# SCH_MyBusinessCard_2024-10-20.net
KiCad netlist of a schematic drawn in EasyEDA
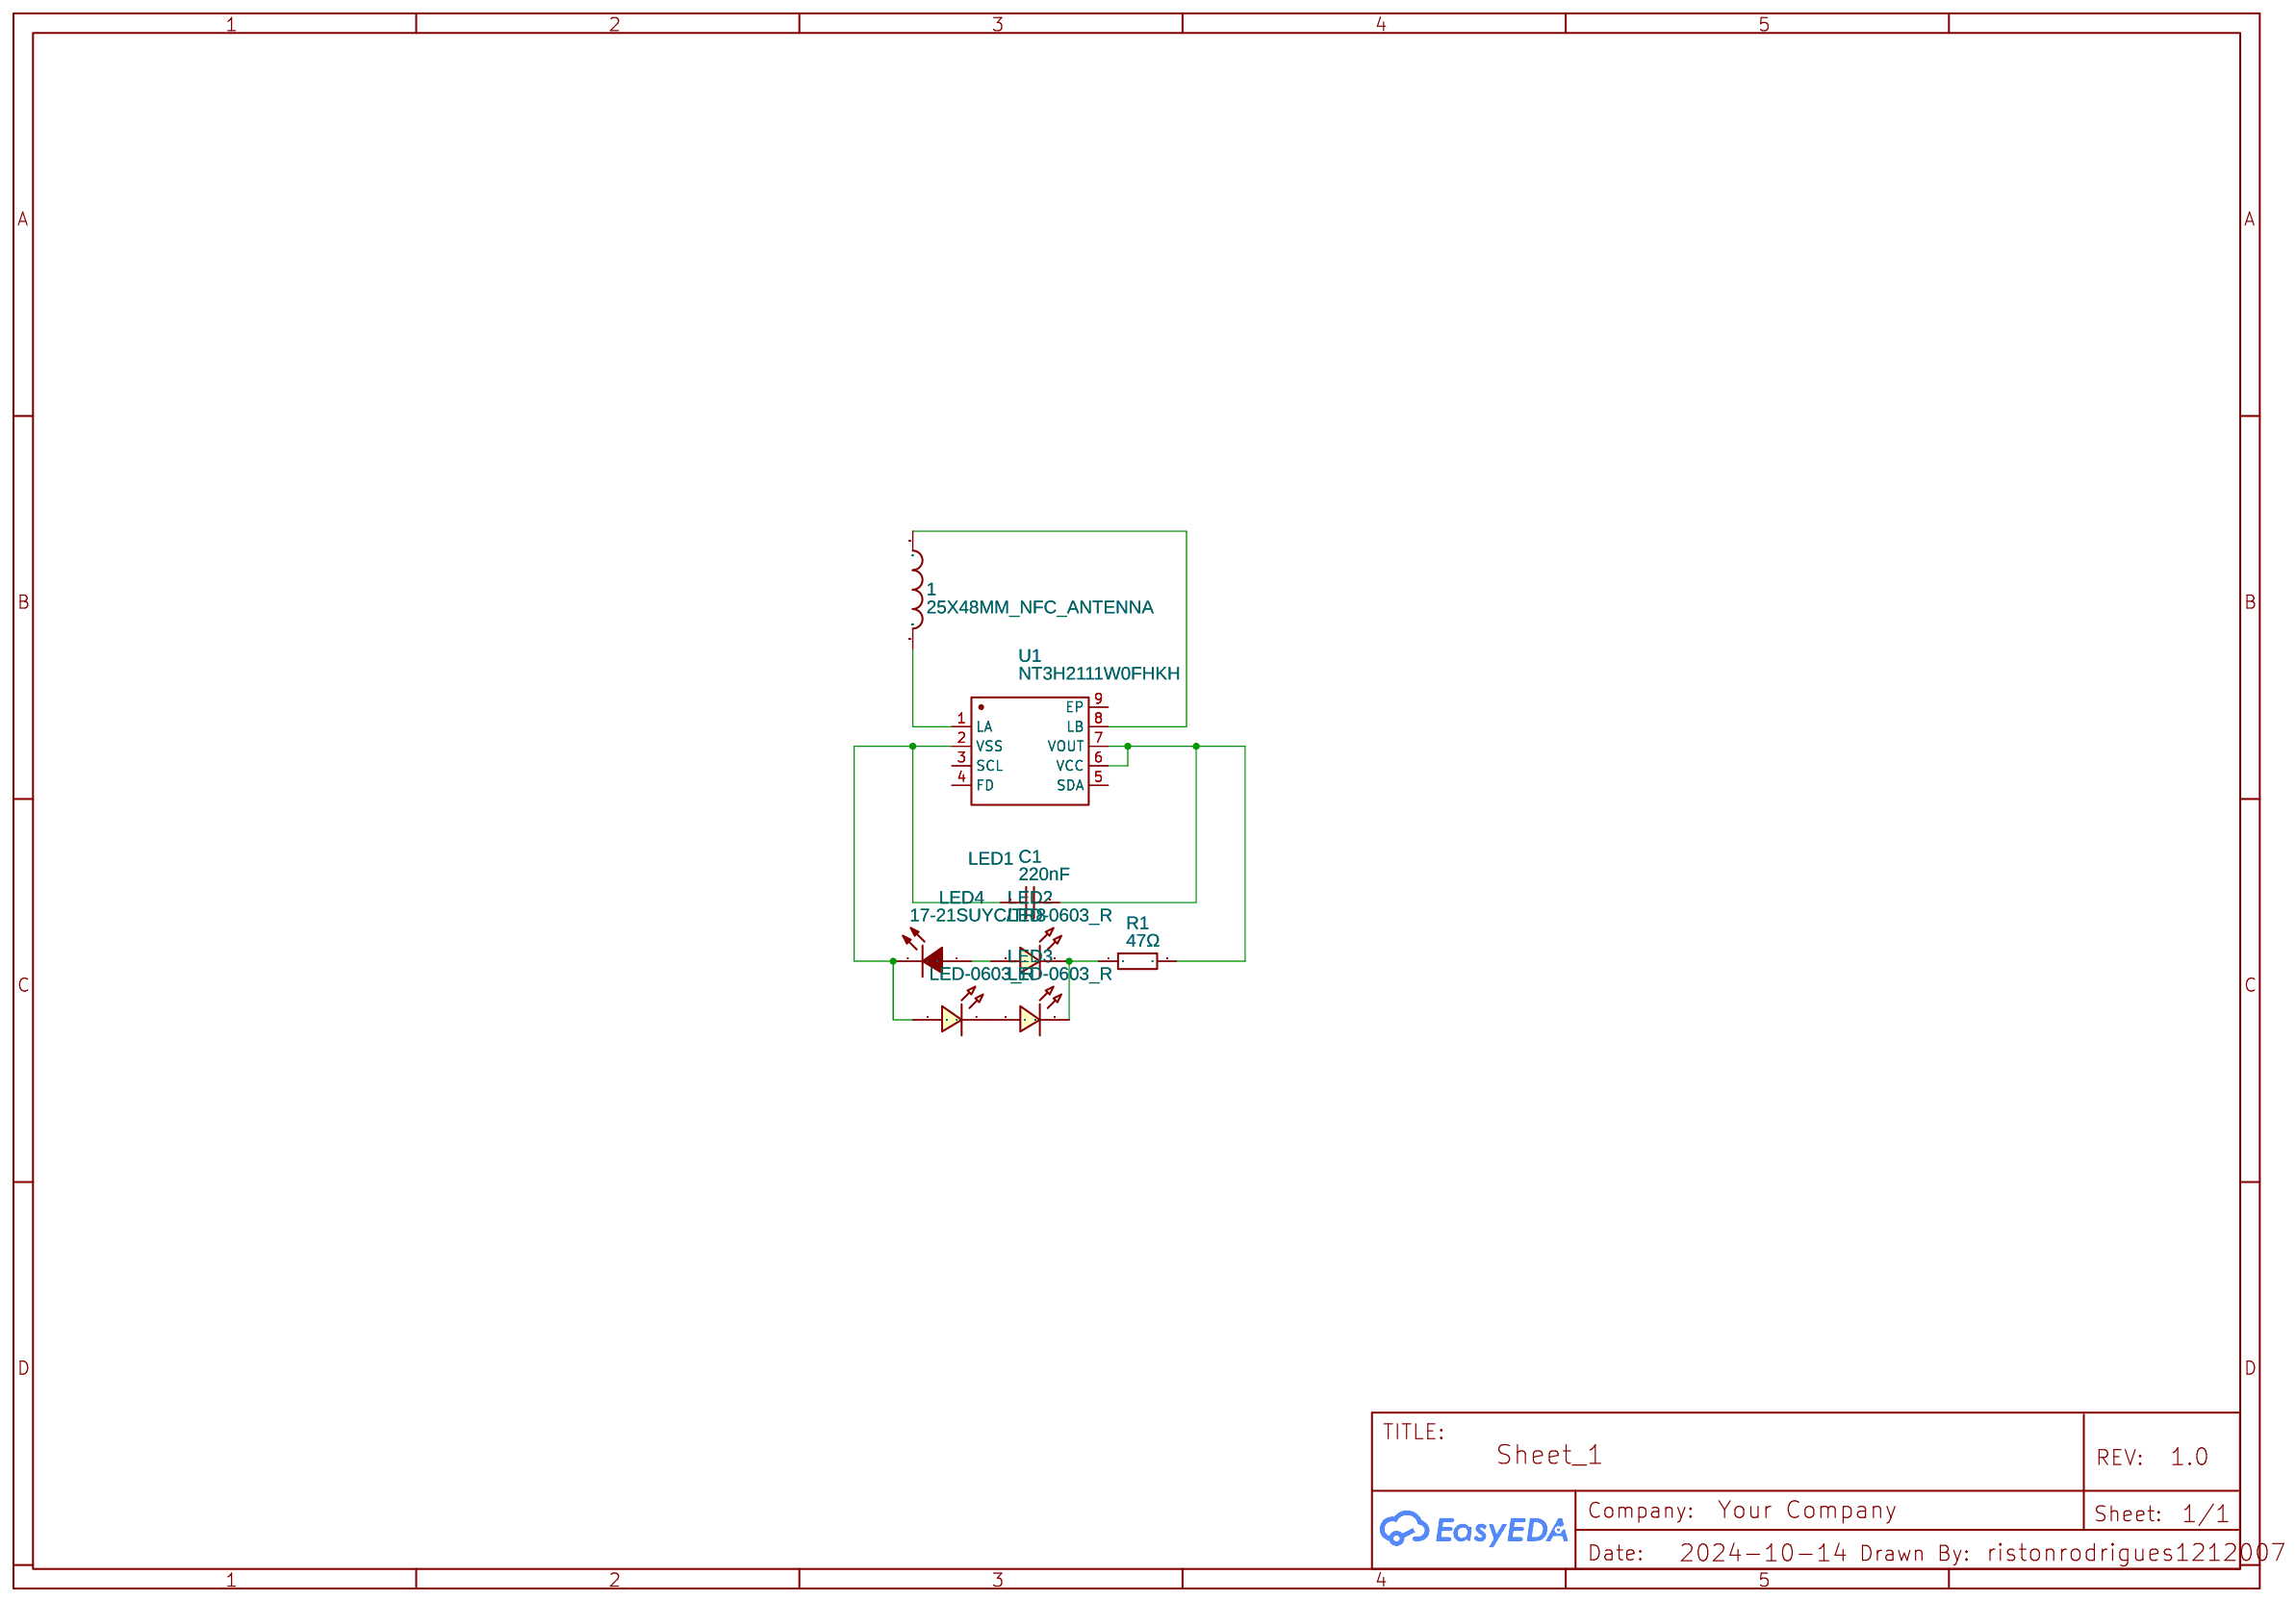
[diagram p0: schematic sheet]

(export (version "E")
  (design (tool "Eeschema 10.0.6"))
  (components
    (comp (ref "1") (value "25X48MM_NFC_ANTENNA") (libsource (lib "") (part "25X48MM_NFC_ANTENNA")))
    (comp (ref "C1")
      (value "220nF")
      (fields
        (field (name "Manufacturer Part") "CL10B224KA8NNNC")
        (field (name "Manufacturer") "SAMSUNG(三星)")
      )
      (libsource (lib "") (part "CL10B224KA8NNNC"))
    )
    (comp (ref "LED1")
      (value "17-21SUYC/TR8")
      (fields (field (name "Manufacturer Part") "KT-0805黄灯") (field (name "Manufacturer") "KENTO"))
      (libsource (lib "") (part "17-21SUYC/TR8"))
    )
    (comp (ref "LED2")
      (value "LED-0603_R")
      (fields
        (field (name "Manufacturer Part") "19-217/R6C-AL1M2VY/3T")
        (field (name "Manufacturer") "EVERLIGHT(台湾亿光)")
      )
      (libsource (lib "") (part "LED-0603_R"))
    )
    (comp (ref "LED3")
      (value "LED-0603_R")
      (fields
        (field (name "Manufacturer Part") "19-217/R6C-AL1M2VY/3T")
        (field (name "Manufacturer") "EVERLIGHT(台湾亿光)")
      )
      (libsource (lib "") (part "LED-0603_R"))
    )
    (comp (ref "LED4")
      (value "LED-0603_R")
      (fields
        (field (name "Manufacturer Part") "19-217/R6C-AL1M2VY/3T")
        (field (name "Manufacturer") "EVERLIGHT(台湾亿光)")
      )
      (libsource (lib "") (part "LED-0603_R"))
    )
    (comp (ref "R1")
      (value "47Ω")
      (fields
        (field (name "Manufacturer Part") "0603WAF470JT5E")
        (field (name "Manufacturer") "UNI-ROYAL(厚声)")
      )
      (libsource (lib "") (part "0603WAF470JT5E"))
    )
    (comp (ref "U1")
      (value "NT3H2111W0FHKH")
      (fields (field (name "Manufacturer") "NXP(恩智浦)"))
      (libsource (lib "") (part "NT3H2111W0FHKH"))
    )
  )
  (nets
    (net (code "1") (name "Net-(LED1-+)") (class "Default")
      (node (ref "LED1") (pin "1") (pinfunction "+_1") (pintype "unspecified"))
      (node (ref "LED2") (pin "1") (pinfunction "1_1") (pintype "unspecified"))
    )
    (net (code "2") (name "Net-(LED1--)") (class "Default")
      (node (ref "C1") (pin "1") (pinfunction "1_1") (pintype "input"))
      (node (ref "LED1") (pin "2") (pinfunction "-_2") (pintype "unspecified"))
      (node (ref "LED4") (pin "1") (pinfunction "1_1") (pintype "unspecified"))
      (node (ref "U1") (pin "2") (pinfunction "VSS_2") (pintype "unspecified"))
    )
    (net (code "3") (name "Net-(LED2-Pad2)") (class "Default")
      (node (ref "LED2") (pin "2") (pinfunction "2_2") (pintype "unspecified"))
      (node (ref "LED3") (pin "2") (pinfunction "2_2") (pintype "unspecified"))
      (node (ref "R1") (pin "1") (pinfunction "1_1") (pintype "input"))
    )
    (net (code "4") (name "Net-(LED3-Pad1)") (class "Default")
      (node (ref "LED3") (pin "1") (pinfunction "1_1") (pintype "unspecified"))
      (node (ref "LED4") (pin "2") (pinfunction "2_2") (pintype "unspecified"))
    )
    (net (code "5") (name "Net-(U1-LA)") (class "Default")
      (node (ref "1") (pin "P$2") (pinfunction "P$2_P$2") (pintype "bidirectional"))
      (node (ref "U1") (pin "1") (pinfunction "LA_1") (pintype "unspecified"))
    )
    (net (code "6") (name "Net-(U1-LB)") (class "Default")
      (node (ref "1") (pin "P$1") (pinfunction "P$1_P$1") (pintype "bidirectional"))
      (node (ref "U1") (pin "8") (pinfunction "LB_8") (pintype "unspecified"))
    )
    (net (code "7") (name "Net-(U1-VCC)") (class "Default")
      (node (ref "C1") (pin "2") (pinfunction "2_2") (pintype "input"))
      (node (ref "R1") (pin "2") (pinfunction "2_2") (pintype "input"))
      (node (ref "U1") (pin "6") (pinfunction "VCC_6") (pintype "unspecified"))
      (node (ref "U1") (pin "7") (pinfunction "VOUT_7") (pintype "unspecified"))
    )
    (net (code "8") (name "unconnected-(U1-EP-Pad9)") (class "Default")
      (node (ref "U1") (pin "9") (pinfunction "EP_9") (pintype "unspecified"))
    )
    (net (code "9") (name "unconnected-(U1-FD-Pad4)") (class "Default")
      (node (ref "U1") (pin "4") (pinfunction "FD_4") (pintype "unspecified"))
    )
    (net (code "10") (name "unconnected-(U1-SCL-Pad3)") (class "Default")
      (node (ref "U1") (pin "3") (pinfunction "SCL_3") (pintype "unspecified"))
    )
    (net (code "11") (name "unconnected-(U1-SDA-Pad5)") (class "Default")
      (node (ref "U1") (pin "5") (pinfunction "SDA_5") (pintype "unspecified"))
    )
  )
)
